# X16R60.net
KiCad netlist of a schematic drawn in EAGLE
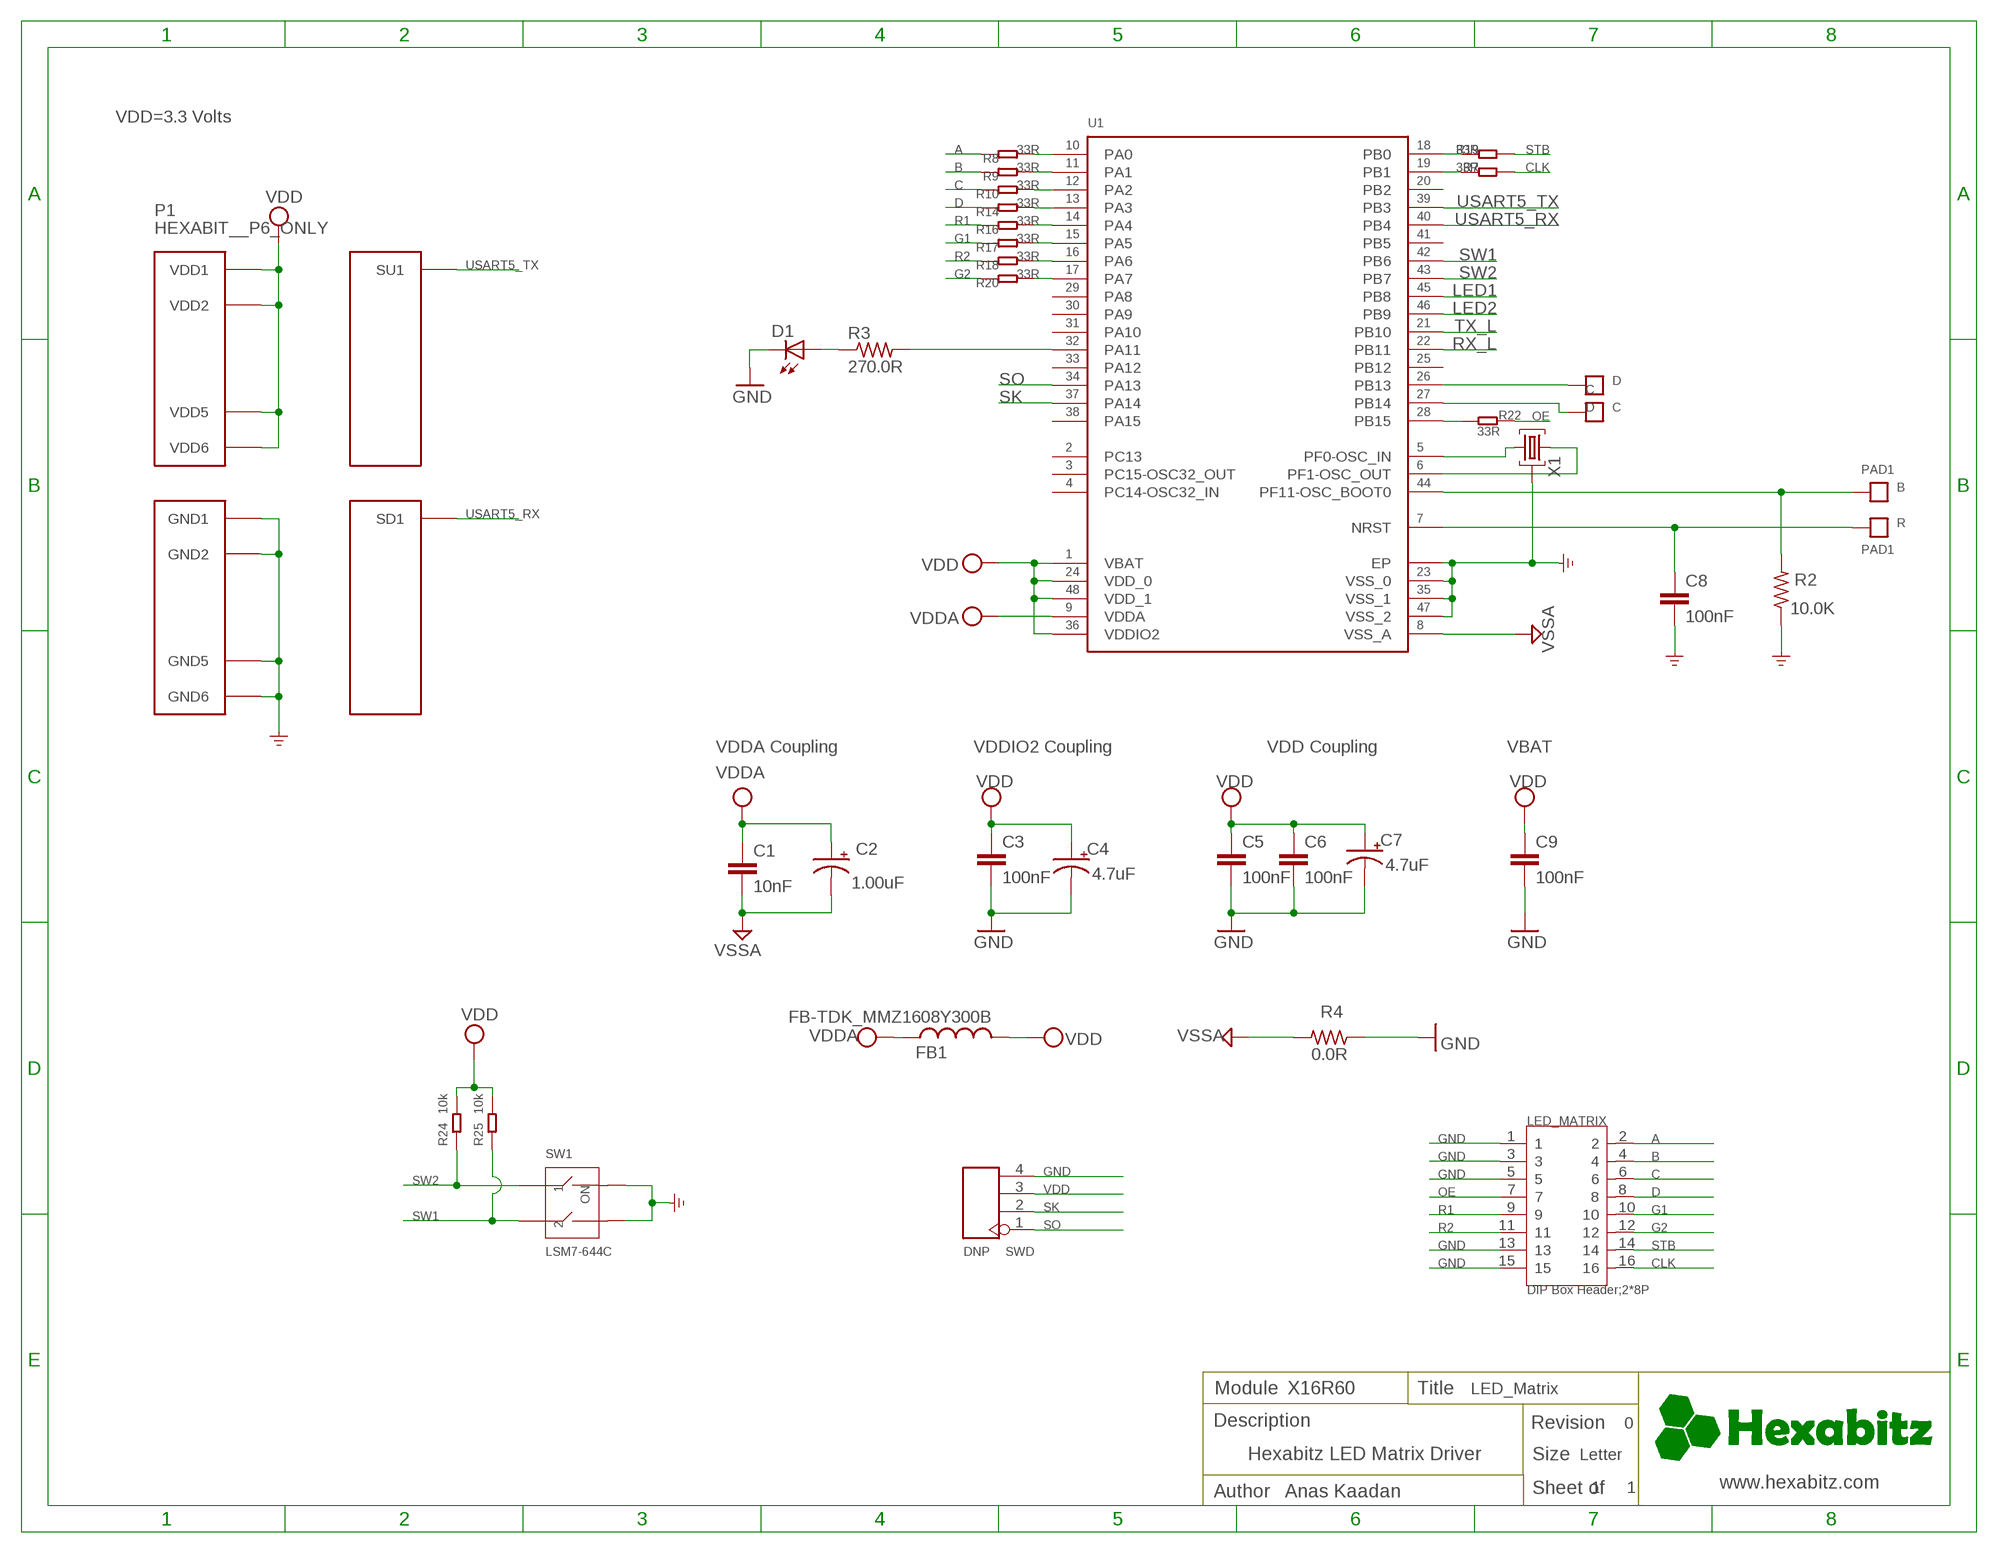
[diagram p0: schematic, sheet 1]

(export (version "E")
  (design (tool "Eeschema 10.0.6"))
  (components
    (comp (ref "B")
      (value "PAD1")
      (footprint "eagle-import:PAD1")
      (libsource (lib "eagle-import") (part "PAD1"))
    )
    (comp (ref "C")
      (value "C")
      (footprint "eagle-import:PAD1")
      (libsource (lib "eagle-import") (part "PAD1"))
    )
    (comp (ref "C1")
      (value "10nF")
      (footprint "eagle-import:C-0603")
      (fields
        (field (name "CAPACITANCE") "10nF")
        (field (name "MFN") "KEMET")
        (field (name "MPN") "C0603C103K5RACTU")
        (field (name "OCTOPART_URL") "https://octopart.com/c0603c103k5ractu-kemet-133094?r=sp&s=R_iPBxLnSmGqhkU2rIMFpg")
        (field (name "TOLERANCE") "10%")
        (field (name "VOLTAGE_RATING") "50V")
      )
      (libsource (lib "eagle-import") (part "C-0603"))
    )
    (comp (ref "C2")
      (value "1.00uF")
      (footprint "eagle-import:C-0805-POL")
      (fields
        (field (name "CAPACITANCE") "1.00uF")
        (field (name "MFN") "Yageo")
        (field (name "MPN") "CC0805KKX7R7BB105")
        (field (name "OCTOPART_URL") "https://octopart.com/cc0805kkx7r7bb105-yageo-8376555?r=sp&s=YKl1wwtkROau_X5nniH2ig")
        (field (name "TOLERANCE") "10%")
        (field (name "VOLTAGE_RATING") "16V")
      )
      (libsource (lib "eagle-import") (part "C-0805-POL"))
    )
    (comp (ref "C3")
      (value "100nF")
      (footprint "eagle-import:C-0603")
      (fields
        (field (name "CAPACITANCE") "100nF")
        (field (name "MFN") "KEMET")
        (field (name "MPN") "C0603C104K8RACTU")
        (field (name "OCTOPART_URL") "https://octopart.com/c0603c104k8ractu-kemet-145075?r=sp&s=9bS9ASSwSEqMCE9KBEQZ0g")
        (field (name "TOLERANCE") "10%")
        (field (name "VOLTAGE_RATING") "10V")
      )
      (libsource (lib "eagle-import") (part "C-0603"))
    )
    (comp (ref "C4")
      (value "4.7uF")
      (footprint "eagle-import:C-0805-POL")
      (fields
        (field (name "CAPACITANCE") "4.7uF")
        (field (name "MFN") "Murata")
        (field (name "MPN") "GRM21BC81E475KA12L")
        (field (name "OCTOPART_URL") "https://octopart.com/grm21bc81e475ka12l-murata-10331911?r=sp&s=RY3qZSD8T6mG6TC9CHI5qQ")
        (field (name "TOLERANCE") "10%")
        (field (name "VOLTAGE_RATING") "25V")
      )
      (libsource (lib "eagle-import") (part "C-0805-POL"))
    )
    (comp (ref "C5")
      (value "100nF")
      (footprint "eagle-import:C-0603")
      (fields
        (field (name "CAPACITANCE") "100nF")
        (field (name "MFN") "KEMET")
        (field (name "MPN") "C0603C104K8RACTU")
        (field (name "OCTOPART_URL") "https://octopart.com/c0603c104k8ractu-kemet-145075?r=sp&s=9bS9ASSwSEqMCE9KBEQZ0g")
        (field (name "TOLERANCE") "10%")
        (field (name "VOLTAGE_RATING") "10")
      )
      (libsource (lib "eagle-import") (part "C-0603"))
    )
    (comp (ref "C6")
      (value "100nF")
      (footprint "eagle-import:C-0603")
      (fields
        (field (name "CAPACITANCE") "100nF")
        (field (name "MFN") "KEMET")
        (field (name "MPN") "C0603C104K8RACTU")
        (field (name "OCTOPART_URL") "https://octopart.com/c0603c104k8ractu-kemet-145075?r=sp&s=9bS9ASSwSEqMCE9KBEQZ0g")
        (field (name "TOLERANCE") "10%")
        (field (name "VOLTAGE_RATING") "10V")
      )
      (libsource (lib "eagle-import") (part "C-0603"))
    )
    (comp (ref "C7")
      (value "4.7uF")
      (footprint "eagle-import:C-0805-POL")
      (fields
        (field (name "CAPACITANCE") "4.7uF")
        (field (name "MFN") "Murata")
        (field (name "MPN") "GRM21BC81E475KA12L")
        (field (name "OCTOPART_URL") "https://octopart.com/grm21bc81e475ka12l-murata-10331911?r=sp&s=RY3qZSD8T6mG6TC9CHI5qQ")
        (field (name "TOLERANCE") "10%")
        (field (name "VOLTAGE_RATING") "25V")
      )
      (libsource (lib "eagle-import") (part "C-0805-POL"))
    )
    (comp (ref "C8")
      (value "100nF")
      (footprint "eagle-import:C-0603")
      (fields
        (field (name "CAPACITANCE") "100nF")
        (field (name "MFN") "KEMET")
        (field (name "MPN") "C0603C104K8RACTU")
        (field (name "OCTOPART_URL") "https://octopart.com/c0603c104k8ractu-kemet-145075?r=sp&s=9bS9ASSwSEqMCE9KBEQZ0g")
        (field (name "TOLERANCE") "10%")
        (field (name "VOLTAGE_RATING") "10V")
      )
      (libsource (lib "eagle-import") (part "C-0603"))
    )
    (comp (ref "C9")
      (value "100nF")
      (footprint "eagle-import:C-0603")
      (fields
        (field (name "CAPACITANCE") "100nF")
        (field (name "MFN") "KEMET")
        (field (name "MPN") "C0603C104K8RACTU")
        (field (name "OCTOPART_URL") "https://octopart.com/c0603c104k8ractu-kemet-145075?r=sp&s=9bS9ASSwSEqMCE9KBEQZ0g")
        (field (name "TOLERANCE") "10V")
        (field (name "VOLTAGE_RATING") "10%")
      )
      (libsource (lib "eagle-import") (part "C-0603"))
    )
    (comp (ref "D")
      (value "D")
      (footprint "eagle-import:PAD1")
      (libsource (lib "eagle-import") (part "PAD1"))
    )
    (comp (ref "D1")
      (value "VLMS1300-GS08")
      (footprint "eagle-import:VLMS1300-GS08")
      (fields
        (field (name "MFN") "Vishay")
        (field (name "MPN") "VLMS1300-GS08")
        (field (name "OCTOPART_URL") "https://octopart.com/vlms1300-gs08-vishay-21709201?r=sp&s=_gcP4_q8T1SC6PJQPTQ9yA")
      )
      (libsource (lib "eagle-import") (part "VLMS1300-GS08"))
    )
    (comp (ref "FB1")
      (value "FB-TDK_MMZ1608Y300B")
      (footprint "eagle-import:FB-TDK_MMZ1608Y300B")
      (fields
        (field (name "MFN") "TDK ")
        (field (name "MPN") "MMZ1608Y300B")
        (field (name "OCTOPART_URL") "https://octopart.com/mmz1608y300b-tdk-368280?r=sp&s=cd9_2ZEqQ9q9UNBuQgHAiA")
      )
      (libsource (lib "eagle-import") (part "FB-TDK_MMZ1608Y300B"))
    )
    (comp (ref "LED_MATRIX")
      (value "DIP Box Header;2*8P")
      (footprint "eagle-import:H2X8_2.54")
      (description "2.54mm Straight 2X8p 16pin Box Header")
      (libsource (lib "eagle-import") (part "HEADER-2X8P"))
    )
    (comp (ref "P1")
      (value "HEXABIT__P6_ONLY")
      (footprint "eagle-import:HEXABIT_17.32_P6_ONLY")
      (libsource (lib "eagle-import") (part "HEXABIT_?_P6_ONLY"))
    )
    (comp (ref "R")
      (value "PAD1")
      (footprint "eagle-import:PAD1")
      (libsource (lib "eagle-import") (part "PAD1"))
    )
    (comp (ref "R2")
      (value "10.0K")
      (footprint "eagle-import:R-0603")
      (fields
        (field (name "MFN") "Yageo")
        (field (name "MPN") "RC0603JR-0710KL")
        (field (name "OCTOPART_URL") "https://octopart.com/search?q=RC0603JR-0710KL&start=0")
        (field (name "RESISTANCE") "10.0K Ohm")
        (field (name "TOLERANCE") "5%")
      )
      (libsource (lib "eagle-import") (part "R-0603"))
    )
    (comp (ref "R3")
      (value "270.0R")
      (footprint "eagle-import:R-0603")
      (fields
        (field (name "MFN") "Yageo")
        (field (name "MPN") "RC0603FR-07270RL")
        (field (name "OCTOPART_URL") "https://octopart.com/search?q=RC0603FR-07270RL&start=0")
        (field (name "RESISTANCE") "270.0 Ohm")
        (field (name "TOLERANCE") "1%")
      )
      (libsource (lib "eagle-import") (part "R-0603"))
    )
    (comp (ref "R4")
      (value "0.0R")
      (footprint "eagle-import:R-0603")
      (fields
        (field (name "MFN") "Yageo")
        (field (name "MPN") "RC0603JR-070RL")
        (field (name "OCTOPART_URL") "https://octopart.com/rc0603jr-070rl-yageo-1241539?r=sp&s=X2NteqRjRNWrnx42Y0aliA")
        (field (name "RESISTANCE") "0.0 Ohm")
      )
      (libsource (lib "eagle-import") (part "R-0603"))
    )
    (comp (ref "R7")
      (value "33R")
      (footprint "eagle-import:R0402")
      (description "Res Thick Film 0402 33 Ohm 1% 0.063W(1/16W) ±100ppm/C Pad SMD Automotive T/R")
      (fields (field (name "MPN") "AC0402FR-0733RL"))
      (libsource (lib "eagle-import") (part "RES-0402"))
    )
    (comp (ref "R8")
      (value "33R")
      (footprint "eagle-import:R0402")
      (description "Res Thick Film 0402 33 Ohm 1% 0.063W(1/16W) ±100ppm/C Pad SMD Automotive T/R")
      (fields (field (name "MPN") "AC0402FR-0733RL"))
      (libsource (lib "eagle-import") (part "RES-0402"))
    )
    (comp (ref "R9")
      (value "33R")
      (footprint "eagle-import:R0402")
      (description "Res Thick Film 0402 33 Ohm 1% 0.063W(1/16W) ±100ppm/C Pad SMD Automotive T/R")
      (fields (field (name "MPN") "AC0402FR-0733RL"))
      (libsource (lib "eagle-import") (part "RES-0402"))
    )
    (comp (ref "R10")
      (value "33R")
      (footprint "eagle-import:R0402")
      (description "Res Thick Film 0402 33 Ohm 1% 0.063W(1/16W) ±100ppm/C Pad SMD Automotive T/R")
      (fields (field (name "MPN") "AC0402FR-0733RL"))
      (libsource (lib "eagle-import") (part "RES-0402"))
    )
    (comp (ref "R14")
      (value "33R")
      (footprint "eagle-import:R0402")
      (description "Res Thick Film 0402 33 Ohm 1% 0.063W(1/16W) ±100ppm/C Pad SMD Automotive T/R")
      (fields (field (name "MPN") "AC0402FR-0733RL"))
      (libsource (lib "eagle-import") (part "RES-0402"))
    )
    (comp (ref "R16")
      (value "33R")
      (footprint "eagle-import:R0402")
      (description "Res Thick Film 0402 33 Ohm 1% 0.063W(1/16W) ±100ppm/C Pad SMD Automotive T/R")
      (fields (field (name "MPN") "AC0402FR-0733RL"))
      (libsource (lib "eagle-import") (part "RES-0402"))
    )
    (comp (ref "R17")
      (value "33R")
      (footprint "eagle-import:R0402")
      (description "Res Thick Film 0402 33 Ohm 1% 0.063W(1/16W) ±100ppm/C Pad SMD Automotive T/R")
      (fields (field (name "MPN") "AC0402FR-0733RL"))
      (libsource (lib "eagle-import") (part "RES-0402"))
    )
    (comp (ref "R18")
      (value "33R")
      (footprint "eagle-import:R0402")
      (description "Res Thick Film 0402 33 Ohm 1% 0.063W(1/16W) ±100ppm/C Pad SMD Automotive T/R")
      (fields (field (name "MPN") "AC0402FR-0733RL"))
      (libsource (lib "eagle-import") (part "RES-0402"))
    )
    (comp (ref "R19")
      (value "33R")
      (footprint "eagle-import:R0402")
      (description "Res Thick Film 0402 33 Ohm 1% 0.063W(1/16W) ±100ppm/C Pad SMD Automotive T/R")
      (fields (field (name "MPN") "AC0402FR-0733RL"))
      (libsource (lib "eagle-import") (part "RES-0402"))
    )
    (comp (ref "R20")
      (value "33R")
      (footprint "eagle-import:R0402")
      (fields (field (name "MPN") "AC0402FR-0733RL"))
      (libsource (lib "eagle-import") (part "RES-0402"))
    )
    (comp (ref "R22")
      (value "33R")
      (footprint "eagle-import:R0402")
      (description "Res Thick Film 0402 33 Ohm 1% 0.063W(1/16W) ±100ppm/C Pad SMD Automotive T/R")
      (fields (field (name "MPN") "AC0402FR-0733RL"))
      (libsource (lib "eagle-import") (part "RES-0402"))
    )
    (comp (ref "R24")
      (value "10k")
      (footprint "eagle-import:R0402")
      (fields (field (name "MPN") "RC0402FR-07510KL"))
      (libsource (lib "eagle-import") (part "RES-0402"))
    )
    (comp (ref "R25")
      (value "10k")
      (footprint "eagle-import:R0402")
      (description "General Purpose Chip Resistor Thick Film 0402 510kOhm 1% Paper T/R")
      (fields (field (name "MPN") "RC0402FR-07510KL"))
      (libsource (lib "eagle-import") (part "RES-0402"))
    )
    (comp (ref "SW1")
      (value "LSM7-644C")
      (footprint "eagle-import:SW4-SMD-2.54-5.08X6.8X3.3MM")
      (description "Switch DIP OFF ON SPST 2 Raised Slide 0.025A 24VDC Gull Wing 2.54mm SMD T/R")
      (fields (field (name "MPN") "KAE02LGGR"))
      (libsource (lib "eagle-import") (part "SWITCHES-2X2P'KM-02'"))
    )
    (comp (ref "SWD")
      (value "DNP")
      (footprint "eagle-import:H4-2.54")
      (libsource (lib "eagle-import") (part "HEADER-4P-65/35MIL"))
    )
    (comp (ref "U1")
      (value "STM32F091CBU6")
      (footprint "eagle-import:STM32F091CBU6")
      (libsource (lib "eagle-import") (part "STM32F091CBU6"))
    )
    (comp (ref "X1")
      (value "XTALL_CSTCE8M00G52")
      (footprint "eagle-import:XTALL_CSTCE8M00G52")
      (fields (field (name "MPN") "CSTCE8M00G52Z-R0"))
      (libsource (lib "eagle-import") (part "XTALL_CSTCE8M00G52"))
    )
  )
  (nets
    (net (code "1") (name "/A") (class "Default")
      (node (ref "LED_MATRIX") (pin "2") (pinfunction "2_2") (pintype "bidirectional"))
      (node (ref "R8") (pin "1") (pinfunction "1_1") (pintype "passive"))
    )
    (net (code "2") (name "/B") (class "Default")
      (node (ref "LED_MATRIX") (pin "4") (pinfunction "4_4") (pintype "bidirectional"))
      (node (ref "R9") (pin "1") (pinfunction "1_1") (pintype "passive"))
    )
    (net (code "3") (name "/C") (class "Default")
      (node (ref "LED_MATRIX") (pin "6") (pinfunction "6_6") (pintype "bidirectional"))
      (node (ref "R10") (pin "1") (pinfunction "1_1") (pintype "passive"))
    )
    (net (code "4") (name "/CLK") (class "Default")
      (node (ref "LED_MATRIX") (pin "16") (pinfunction "16_16") (pintype "bidirectional"))
      (node (ref "R7") (pin "2") (pinfunction "2_2") (pintype "passive"))
    )
    (net (code "5") (name "/D") (class "Default")
      (node (ref "LED_MATRIX") (pin "8") (pinfunction "8_8") (pintype "bidirectional"))
      (node (ref "R14") (pin "1") (pinfunction "1_1") (pintype "passive"))
    )
    (net (code "6") (name "/G1") (class "Default")
      (node (ref "LED_MATRIX") (pin "10") (pinfunction "10_10") (pintype "bidirectional"))
      (node (ref "R17") (pin "1") (pinfunction "1_1") (pintype "passive"))
    )
    (net (code "7") (name "/G2") (class "Default")
      (node (ref "LED_MATRIX") (pin "12") (pinfunction "12_12") (pintype "bidirectional"))
      (node (ref "R20") (pin "2") (pinfunction "2_2") (pintype "passive"))
    )
    (net (code "8") (name "/LED1") (class "Default")
      (node (ref "U1") (pin "P$45") (pinfunction "PB8_P$45") (pintype "bidirectional"))
    )
    (net (code "9") (name "/LED2") (class "Default")
      (node (ref "U1") (pin "P$46") (pinfunction "PB9_P$46") (pintype "bidirectional"))
    )
    (net (code "10") (name "/OE") (class "Default")
      (node (ref "LED_MATRIX") (pin "7") (pinfunction "7_7") (pintype "bidirectional"))
      (node (ref "R22") (pin "2") (pinfunction "2_2") (pintype "passive"))
    )
    (net (code "11") (name "/R1") (class "Default")
      (node (ref "LED_MATRIX") (pin "9") (pinfunction "9_9") (pintype "bidirectional"))
      (node (ref "R16") (pin "1") (pinfunction "1_1") (pintype "passive"))
    )
    (net (code "12") (name "/R2") (class "Default")
      (node (ref "LED_MATRIX") (pin "11") (pinfunction "11_11") (pintype "bidirectional"))
      (node (ref "R18") (pin "1") (pinfunction "1_1") (pintype "passive"))
    )
    (net (code "13") (name "/RX_L") (class "Default")
      (node (ref "U1") (pin "P$22") (pinfunction "PB11_P$22") (pintype "bidirectional"))
    )
    (net (code "14") (name "/SK") (class "Default")
      (node (ref "SWD") (pin "2") (pinfunction "P$2_2") (pintype "bidirectional"))
      (node (ref "U1") (pin "P$37") (pinfunction "PA14_P$37") (pintype "bidirectional"))
    )
    (net (code "15") (name "/SO") (class "Default")
      (node (ref "SWD") (pin "1") (pinfunction "P$1_1") (pintype "bidirectional"))
      (node (ref "U1") (pin "P$34") (pinfunction "PA13_P$34") (pintype "bidirectional"))
    )
    (net (code "16") (name "/STB") (class "Default")
      (node (ref "LED_MATRIX") (pin "14") (pinfunction "14_14") (pintype "bidirectional"))
      (node (ref "R19") (pin "2") (pinfunction "2_2") (pintype "passive"))
    )
    (net (code "17") (name "/SW1") (class "Default")
      (node (ref "R25") (pin "1") (pinfunction "1_1") (pintype "passive"))
      (node (ref "SW1") (pin "2") (pinfunction "2_2") (pintype "bidirectional"))
      (node (ref "U1") (pin "P$42") (pinfunction "PB6_P$42") (pintype "bidirectional"))
    )
    (net (code "18") (name "/SW2") (class "Default")
      (node (ref "R24") (pin "1") (pinfunction "1_1") (pintype "passive"))
      (node (ref "SW1") (pin "1") (pinfunction "1_1") (pintype "bidirectional"))
      (node (ref "U1") (pin "P$43") (pinfunction "PB7_P$43") (pintype "bidirectional"))
    )
    (net (code "19") (name "/TX_L") (class "Default")
      (node (ref "U1") (pin "P$21") (pinfunction "PB10_P$21") (pintype "bidirectional"))
    )
    (net (code "20") (name "/USART5_RX") (class "Default")
      (node (ref "P1") (pin "PAD_PD3") (pinfunction "SD1_PAD_PD3") (pintype "bidirectional"))
      (node (ref "U1") (pin "P$40") (pinfunction "PB4_P$40") (pintype "bidirectional"))
    )
    (net (code "21") (name "/USART5_TX") (class "Default")
      (node (ref "P1") (pin "PAD_PU3") (pinfunction "SU1_PAD_PU3") (pintype "bidirectional"))
      (node (ref "U1") (pin "P$39") (pinfunction "PB3_P$39") (pintype "bidirectional"))
    )
    (net (code "22") (name "GND") (class "Default")
      (node (ref "C3") (pin "2") (pinfunction "2_2") (pintype "passive"))
      (node (ref "C4") (pin "2") (pinfunction "-_2") (pintype "passive"))
      (node (ref "C5") (pin "2") (pinfunction "2_2") (pintype "passive"))
      (node (ref "C6") (pin "2") (pinfunction "2_2") (pintype "passive"))
      (node (ref "C7") (pin "2") (pinfunction "-_2") (pintype "passive"))
      (node (ref "C8") (pin "2") (pinfunction "2_2") (pintype "passive"))
      (node (ref "C9") (pin "2") (pinfunction "2_2") (pintype "passive"))
      (node (ref "D1") (pin "C") (pinfunction "C_C") (pintype "passive"))
      (node (ref "LED_MATRIX") (pin "1") (pinfunction "1_1") (pintype "bidirectional"))
      (node (ref "LED_MATRIX") (pin "13") (pinfunction "13_13") (pintype "bidirectional"))
      (node (ref "LED_MATRIX") (pin "15") (pinfunction "15_15") (pintype "bidirectional"))
      (node (ref "LED_MATRIX") (pin "3") (pinfunction "3_3") (pintype "bidirectional"))
      (node (ref "LED_MATRIX") (pin "5") (pinfunction "5_5") (pintype "bidirectional"))
      (node (ref "P1") (pin "PAD_PD10") (pinfunction "GND5_PAD_PD10") (pintype "power_in"))
      (node (ref "P1") (pin "PAD_PD11") (pinfunction "GND6_PAD_PD11") (pintype "power_in"))
      (node (ref "P1") (pin "PAD_PD8") (pinfunction "GND1_PAD_PD8") (pintype "power_in"))
      (node (ref "P1") (pin "PAD_PD9") (pinfunction "GND2_PAD_PD9") (pintype "power_in"))
      (node (ref "R2") (pin "1") (pinfunction "1_1") (pintype "passive"))
      (node (ref "R4") (pin "1") (pinfunction "1_1") (pintype "passive"))
      (node (ref "SW1") (pin "3") (pinfunction "3_3") (pintype "bidirectional"))
      (node (ref "SW1") (pin "4") (pinfunction "4_4") (pintype "bidirectional"))
      (node (ref "SWD") (pin "4") (pinfunction "P$4_4") (pintype "bidirectional"))
      (node (ref "U1") (pin "EP") (pinfunction "EP_EP") (pintype "power_in"))
      (node (ref "U1") (pin "P$23") (pinfunction "VSS_0_P$23") (pintype "power_in"))
      (node (ref "U1") (pin "P$35") (pinfunction "VSS_1_P$35") (pintype "power_in"))
      (node (ref "U1") (pin "P$47") (pinfunction "VSS_2_P$47") (pintype "power_in"))
      (node (ref "X1") (pin "P$2") (pinfunction "2_P$2") (pintype "passive"))
    )
    (net (code "23") (name "Net-(D1-PadA)") (class "Default")
      (node (ref "D1") (pin "A") (pinfunction "A_A") (pintype "passive"))
      (node (ref "R3") (pin "1") (pinfunction "1_1") (pintype "passive"))
    )
    (net (code "24") (name "Net-(U1-NRST)") (class "Default")
      (node (ref "C8") (pin "1") (pinfunction "1_1") (pintype "passive"))
      (node (ref "R") (pin "P$1") (pinfunction "P$1_P$1") (pintype "passive"))
      (node (ref "R") (pin "P$2") (pinfunction "P$1_P$2") (pintype "passive"))
      (node (ref "U1") (pin "P$7") (pinfunction "NRST_P$7") (pintype "passive"))
    )
    (net (code "25") (name "Net-(U1-PA0)") (class "Default")
      (node (ref "R8") (pin "2") (pinfunction "2_2") (pintype "passive"))
      (node (ref "U1") (pin "P$10") (pinfunction "PA0_P$10") (pintype "bidirectional"))
    )
    (net (code "26") (name "Net-(U1-PA1)") (class "Default")
      (node (ref "R9") (pin "2") (pinfunction "2_2") (pintype "passive"))
      (node (ref "U1") (pin "P$11") (pinfunction "PA1_P$11") (pintype "bidirectional"))
    )
    (net (code "27") (name "Net-(U1-PA2)") (class "Default")
      (node (ref "R10") (pin "2") (pinfunction "2_2") (pintype "passive"))
      (node (ref "U1") (pin "P$12") (pinfunction "PA2_P$12") (pintype "bidirectional"))
    )
    (net (code "28") (name "Net-(U1-PA3)") (class "Default")
      (node (ref "R14") (pin "2") (pinfunction "2_2") (pintype "passive"))
      (node (ref "U1") (pin "P$13") (pinfunction "PA3_P$13") (pintype "bidirectional"))
    )
    (net (code "29") (name "Net-(U1-PA4)") (class "Default")
      (node (ref "R16") (pin "2") (pinfunction "2_2") (pintype "passive"))
      (node (ref "U1") (pin "P$14") (pinfunction "PA4_P$14") (pintype "bidirectional"))
    )
    (net (code "30") (name "Net-(U1-PA5)") (class "Default")
      (node (ref "R17") (pin "2") (pinfunction "2_2") (pintype "passive"))
      (node (ref "U1") (pin "P$15") (pinfunction "PA5_P$15") (pintype "bidirectional"))
    )
    (net (code "31") (name "Net-(U1-PA6)") (class "Default")
      (node (ref "R18") (pin "2") (pinfunction "2_2") (pintype "passive"))
      (node (ref "U1") (pin "P$16") (pinfunction "PA6_P$16") (pintype "bidirectional"))
    )
    (net (code "32") (name "Net-(U1-PA7)") (class "Default")
      (node (ref "R20") (pin "1") (pinfunction "1_1") (pintype "passive"))
      (node (ref "U1") (pin "P$17") (pinfunction "PA7_P$17") (pintype "bidirectional"))
    )
    (net (code "33") (name "Net-(U1-PA11)") (class "Default")
      (node (ref "R3") (pin "2") (pinfunction "2_2") (pintype "passive"))
      (node (ref "U1") (pin "P$32") (pinfunction "PA11_P$32") (pintype "bidirectional"))
    )
    (net (code "34") (name "Net-(U1-PB0)") (class "Default")
      (node (ref "R19") (pin "1") (pinfunction "1_1") (pintype "passive"))
      (node (ref "U1") (pin "P$18") (pinfunction "PB0_P$18") (pintype "bidirectional"))
    )
    (net (code "35") (name "Net-(U1-PB1)") (class "Default")
      (node (ref "R7") (pin "1") (pinfunction "1_1") (pintype "passive"))
      (node (ref "U1") (pin "P$19") (pinfunction "PB1_P$19") (pintype "bidirectional"))
    )
    (net (code "36") (name "Net-(U1-PB13)") (class "Default")
      (node (ref "D") (pin "P$1") (pinfunction "P$1_P$1") (pintype "passive"))
      (node (ref "D") (pin "P$2") (pinfunction "P$1_P$2") (pintype "passive"))
      (node (ref "U1") (pin "P$26") (pinfunction "PB13_P$26") (pintype "bidirectional"))
    )
    (net (code "37") (name "Net-(U1-PB14)") (class "Default")
      (node (ref "C") (pin "P$1") (pinfunction "P$1_P$1") (pintype "passive"))
      (node (ref "C") (pin "P$2") (pinfunction "P$1_P$2") (pintype "passive"))
      (node (ref "U1") (pin "P$27") (pinfunction "PB14_P$27") (pintype "bidirectional"))
    )
    (net (code "38") (name "Net-(U1-PB15)") (class "Default")
      (node (ref "R22") (pin "1") (pinfunction "1_1") (pintype "passive"))
      (node (ref "U1") (pin "P$28") (pinfunction "PB15_P$28") (pintype "bidirectional"))
    )
    (net (code "39") (name "Net-(U1-PF0-OSC_IN)") (class "Default")
      (node (ref "U1") (pin "P$5") (pinfunction "PF0-OSC_IN_P$5") (pintype "bidirectional"))
      (node (ref "X1") (pin "P$1") (pinfunction "1_P$1") (pintype "passive"))
    )
    (net (code "40") (name "Net-(U1-PF1-OSC_OUT)") (class "Default")
      (node (ref "U1") (pin "P$6") (pinfunction "PF1-OSC_OUT_P$6") (pintype "bidirectional"))
      (node (ref "X1") (pin "P$3") (pinfunction "3_P$3") (pintype "passive"))
    )
    (net (code "41") (name "Net-(U1-PF11-OSC_BOOT0)") (class "Default")
      (node (ref "B") (pin "P$1") (pinfunction "P$1_P$1") (pintype "passive"))
      (node (ref "B") (pin "P$2") (pinfunction "P$1_P$2") (pintype "passive"))
      (node (ref "R2") (pin "2") (pinfunction "2_2") (pintype "passive"))
      (node (ref "U1") (pin "P$44") (pinfunction "PF11-OSC_BOOT0_P$44") (pintype "bidirectional"))
    )
    (net (code "42") (name "VDD") (class "Default")
      (node (ref "C3") (pin "1") (pinfunction "1_1") (pintype "passive"))
      (node (ref "C4") (pin "1") (pinfunction "+_1") (pintype "passive"))
      (node (ref "C5") (pin "1") (pinfunction "1_1") (pintype "passive"))
      (node (ref "C6") (pin "1") (pinfunction "1_1") (pintype "passive"))
      (node (ref "C7") (pin "1") (pinfunction "+_1") (pintype "passive"))
      (node (ref "C9") (pin "1") (pinfunction "1_1") (pintype "passive"))
      (node (ref "FB1") (pin "2") (pinfunction "2_2") (pintype "passive"))
      (node (ref "P1") (pin "PAD_PU10") (pinfunction "VDD5_PAD_PU10") (pintype "power_in"))
      (node (ref "P1") (pin "PAD_PU11") (pinfunction "VDD6_PAD_PU11") (pintype "power_in"))
      (node (ref "P1") (pin "PAD_PU8") (pinfunction "VDD1_PAD_PU8") (pintype "power_in"))
      (node (ref "P1") (pin "PAD_PU9") (pinfunction "VDD2_PAD_PU9") (pintype "power_in"))
      (node (ref "R24") (pin "2") (pinfunction "2_2") (pintype "passive"))
      (node (ref "R25") (pin "2") (pinfunction "2_2") (pintype "passive"))
      (node (ref "SWD") (pin "3") (pinfunction "P$3_3") (pintype "bidirectional"))
      (node (ref "U1") (pin "P$1") (pinfunction "VBAT_P$1") (pintype "power_in"))
      (node (ref "U1") (pin "P$24") (pinfunction "VDD_0_P$24") (pintype "power_in"))
      (node (ref "U1") (pin "P$36") (pinfunction "VDDIO2_P$36") (pintype "power_in"))
      (node (ref "U1") (pin "P$48") (pinfunction "VDD_1_P$48") (pintype "power_in"))
    )
    (net (code "43") (name "VDDA") (class "Default")
      (node (ref "C1") (pin "1") (pinfunction "1_1") (pintype "passive"))
      (node (ref "C2") (pin "1") (pinfunction "+_1") (pintype "passive"))
      (node (ref "FB1") (pin "1") (pinfunction "1_1") (pintype "passive"))
      (node (ref "U1") (pin "P$9") (pinfunction "VDDA_P$9") (pintype "power_in"))
    )
    (net (code "44") (name "VSSA") (class "Default")
      (node (ref "C1") (pin "2") (pinfunction "2_2") (pintype "passive"))
      (node (ref "C2") (pin "2") (pinfunction "-_2") (pintype "passive"))
      (node (ref "R4") (pin "2") (pinfunction "2_2") (pintype "passive"))
      (node (ref "U1") (pin "P$8") (pinfunction "VSS_A_P$8") (pintype "power_in"))
    )
    (net (code "45") (name "unconnected-(U1-PA8-PadP$29)") (class "Default")
      (node (ref "U1") (pin "P$29") (pinfunction "PA8_P$29") (pintype "bidirectional"))
    )
    (net (code "46") (name "unconnected-(U1-PA9-PadP$30)") (class "Default")
      (node (ref "U1") (pin "P$30") (pinfunction "PA9_P$30") (pintype "bidirectional"))
    )
    (net (code "47") (name "unconnected-(U1-PA10-PadP$31)") (class "Default")
      (node (ref "U1") (pin "P$31") (pinfunction "PA10_P$31") (pintype "bidirectional"))
    )
    (net (code "48") (name "unconnected-(U1-PA12-PadP$33)") (class "Default")
      (node (ref "U1") (pin "P$33") (pinfunction "PA12_P$33") (pintype "bidirectional"))
    )
    (net (code "49") (name "unconnected-(U1-PA15-PadP$38)") (class "Default")
      (node (ref "U1") (pin "P$38") (pinfunction "PA15_P$38") (pintype "bidirectional"))
    )
    (net (code "50") (name "unconnected-(U1-PB2-PadP$20)") (class "Default")
      (node (ref "U1") (pin "P$20") (pinfunction "PB2_P$20") (pintype "bidirectional"))
    )
    (net (code "51") (name "unconnected-(U1-PB5-PadP$41)") (class "Default")
      (node (ref "U1") (pin "P$41") (pinfunction "PB5_P$41") (pintype "bidirectional"))
    )
    (net (code "52") (name "unconnected-(U1-PB12-PadP$25)") (class "Default")
      (node (ref "U1") (pin "P$25") (pinfunction "PB12_P$25") (pintype "bidirectional"))
    )
    (net (code "53") (name "unconnected-(U1-PC13-PadP$2)") (class "Default")
      (node (ref "U1") (pin "P$2") (pinfunction "PC13_P$2") (pintype "bidirectional"))
    )
    (net (code "54") (name "unconnected-(U1-PC14-OSC32_IN-PadP$3)") (class "Default")
      (node (ref "U1") (pin "P$3") (pinfunction "PC14-OSC32_IN_P$3") (pintype "bidirectional"))
    )
    (net (code "55") (name "unconnected-(U1-PC15-OSC32_OUT-PadP$4)") (class "Default")
      (node (ref "U1") (pin "P$4") (pinfunction "PC15-OSC32_OUT_P$4") (pintype "bidirectional"))
    )
  )
)
